# old_main_board.net
KiCad netlist of a schematic drawn in EAGLE
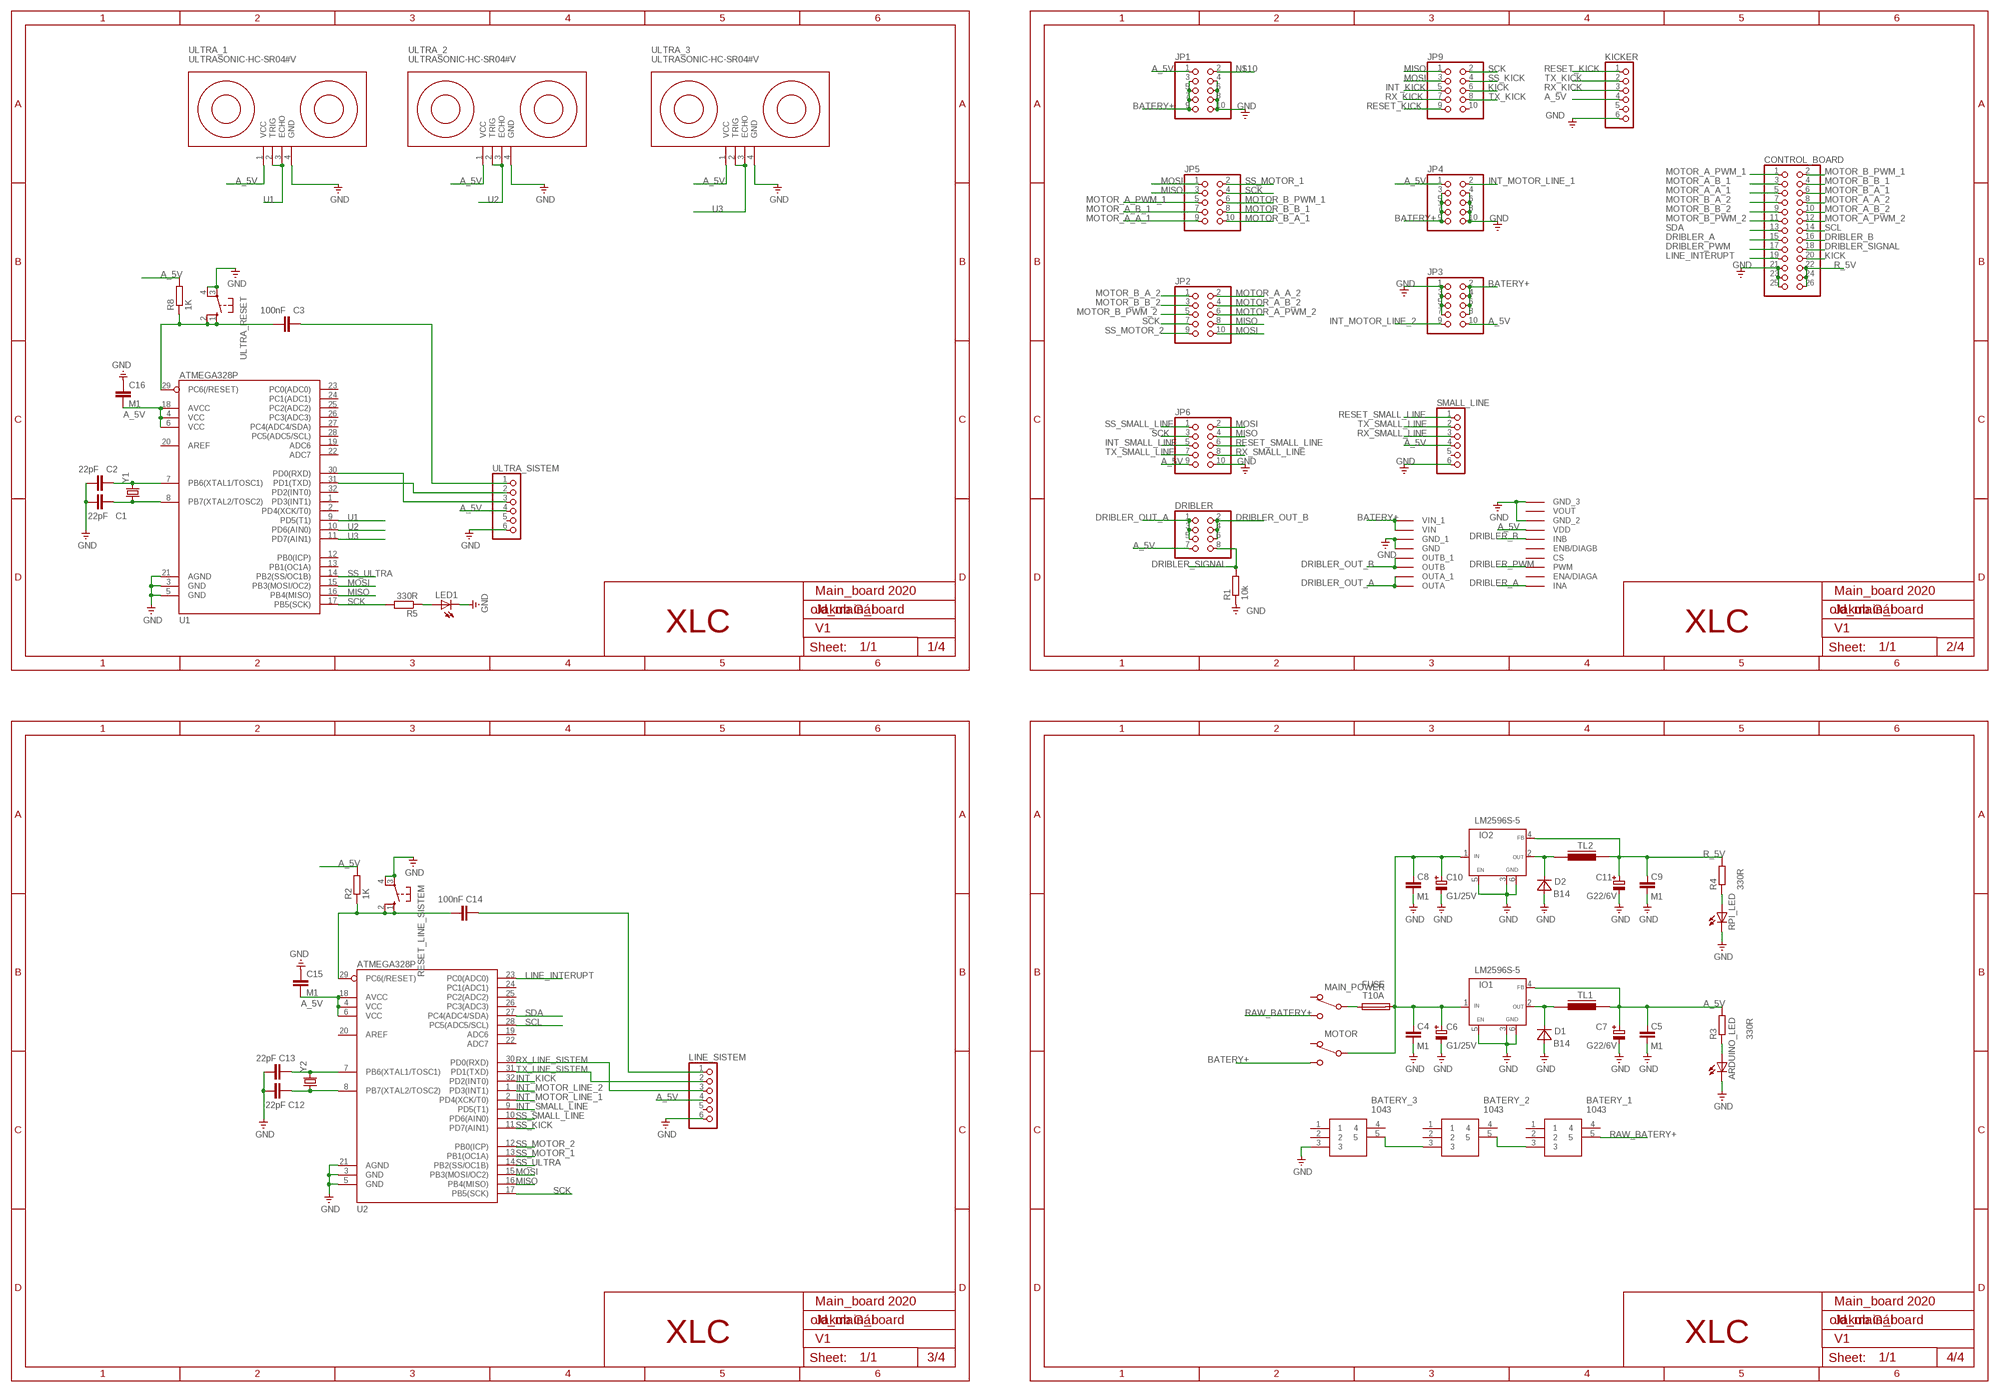
[diagram p0: schematic, sheet 1]

(export (version "E")
  (design (tool "Eeschema 10.0.6"))
  (components
    (comp (ref "ARDUINO_LED")
      (value "LEDCHIPLED_0603")
      (footprint "eagle-import:CHIPLED_0603")
      (libsource (lib "eagle-import") (part "LEDCHIPLED_0603"))
    )
    (comp (ref "BATERY_1")
      (value "1043")
      (footprint "eagle-import:1043")
      (fields (field (name "MOUSER_PART_NUMBER") "534-1043"))
      (libsource (lib "eagle-import") (part "1043"))
    )
    (comp (ref "BATERY_2")
      (value "1043")
      (footprint "eagle-import:1043")
      (fields (field (name "MOUSER_PART_NUMBER") "534-1043"))
      (libsource (lib "eagle-import") (part "1043"))
    )
    (comp (ref "BATERY_3")
      (value "1043")
      (footprint "eagle-import:1043")
      (fields (field (name "MOUSER_PART_NUMBER") "534-1043"))
      (libsource (lib "eagle-import") (part "1043"))
    )
    (comp (ref "C1")
      (value "22pF")
      (footprint "eagle-import:C0603")
      (libsource (lib "eagle-import") (part "rcl@1_C-EUC0603"))
    )
    (comp (ref "C2")
      (value "22pF")
      (footprint "eagle-import:C0603")
      (libsource (lib "eagle-import") (part "rcl@1_C-EUC0603"))
    )
    (comp (ref "C3")
      (value "100nF")
      (footprint "eagle-import:C0603")
      (libsource (lib "eagle-import") (part "rcl@1_C-EUC0603"))
    )
    (comp (ref "C4")
      (value "M1")
      (footprint "eagle-import:SMD-1206")
      (libsource (lib "eagle-import") (part "KOND-KERAM1206-SMD"))
    )
    (comp (ref "C5")
      (value "M1")
      (footprint "eagle-import:SMD-1206")
      (libsource (lib "eagle-import") (part "KOND-KERAM1206-SMD"))
    )
    (comp (ref "C6")
      (value "G1/25V")
      (footprint "eagle-import:SMD-ELE-D")
      (libsource (lib "eagle-import") (part "KOND-ELEKTD-SMD"))
    )
    (comp (ref "C7")
      (value "G22/6V")
      (footprint "eagle-import:SMD-ELE-D")
      (libsource (lib "eagle-import") (part "KOND-ELEKTD-SMD"))
    )
    (comp (ref "C8")
      (value "M1")
      (footprint "eagle-import:SMD-1206")
      (libsource (lib "eagle-import") (part "KOND-KERAM1206-SMD"))
    )
    (comp (ref "C9")
      (value "M1")
      (footprint "eagle-import:SMD-1206")
      (libsource (lib "eagle-import") (part "KOND-KERAM1206-SMD"))
    )
    (comp (ref "C10")
      (value "G1/25V")
      (footprint "eagle-import:SMD-ELE-D")
      (libsource (lib "eagle-import") (part "KOND-ELEKTD-SMD"))
    )
    (comp (ref "C11")
      (value "G22/6V")
      (footprint "eagle-import:SMD-ELE-D")
      (libsource (lib "eagle-import") (part "KOND-ELEKTD-SMD"))
    )
    (comp (ref "C12")
      (value "22pF")
      (footprint "eagle-import:C0603")
      (libsource (lib "eagle-import") (part "rcl@1_C-EUC0603"))
    )
    (comp (ref "C13")
      (value "22pF")
      (footprint "eagle-import:C0603")
      (libsource (lib "eagle-import") (part "rcl@1_C-EUC0603"))
    )
    (comp (ref "C14")
      (value "100nF")
      (footprint "eagle-import:C0603")
      (libsource (lib "eagle-import") (part "rcl@1_C-EUC0603"))
    )
    (comp (ref "C15")
      (value "M1")
      (footprint "eagle-import:C0603")
      (libsource (lib "eagle-import") (part "C-EUC0603"))
    )
    (comp (ref "C16")
      (value "M1")
      (footprint "eagle-import:C0603")
      (libsource (lib "eagle-import") (part "C-EUC0603"))
    )
    (comp (ref "CONTROL_BOARD")
      (value "PINHD-2X13_2.54")
      (footprint "eagle-import:2X13")
      (libsource (lib "eagle-import") (part "PINHD-2X13_2.54"))
    )
    (comp (ref "D1")
      (value "B14")
      (footprint "eagle-import:D-3,6X5,5")
      (libsource (lib "eagle-import") (part "DIODASMD-3,6X5,5"))
    )
    (comp (ref "D2")
      (value "B14")
      (footprint "eagle-import:D-3,6X5,5")
      (libsource (lib "eagle-import") (part "DIODASMD-3,6X5,5"))
    )
    (comp (ref "DRIBLER")
      (value "PINHD-2X4_2.54-SMD")
      (footprint "eagle-import:2X04SMD")
      (libsource (lib "eagle-import") (part "PINHD-2X4_2.54-SMD"))
    )
    (comp (ref "FUSE")
      (value "T10A")
      (footprint "eagle-import:SH22,5A")
      (libsource (lib "eagle-import") (part "POISTKA2A"))
    )
    (comp (ref "IO1")
      (value "LM2596S-5")
      (footprint "eagle-import:TO263-5")
      (libsource (lib "eagle-import") (part "LM2596S"))
    )
    (comp (ref "IO2")
      (value "LM2596S-5")
      (footprint "eagle-import:TO263-5")
      (libsource (lib "eagle-import") (part "LM2596S"))
    )
    (comp (ref "JP1")
      (value "PINHD-2X5IDC")
      (footprint "eagle-import:2X05_IDC")
      (libsource (lib "eagle-import") (part "PINHD-2X5IDC"))
    )
    (comp (ref "JP2")
      (value "PINHD-2X5IDC")
      (footprint "eagle-import:2X05_IDC")
      (libsource (lib "eagle-import") (part "PINHD-2X5IDC"))
    )
    (comp (ref "JP3")
      (value "PINHD-2X5IDC")
      (footprint "eagle-import:2X05_IDC")
      (libsource (lib "eagle-import") (part "PINHD-2X5IDC"))
    )
    (comp (ref "JP4")
      (value "PINHD-2X5IDC")
      (footprint "eagle-import:2X05_IDC")
      (libsource (lib "eagle-import") (part "PINHD-2X5IDC"))
    )
    (comp (ref "JP5")
      (value "PINHD-2X5IDC")
      (footprint "eagle-import:2X05_IDC")
      (libsource (lib "eagle-import") (part "PINHD-2X5IDC"))
    )
    (comp (ref "JP6")
      (value "PINHD-2X5IDC")
      (footprint "eagle-import:2X05_IDC")
      (libsource (lib "eagle-import") (part "PINHD-2X5IDC"))
    )
    (comp (ref "JP9")
      (value "PINHD-2X5IDC")
      (footprint "eagle-import:2X05_IDC")
      (libsource (lib "eagle-import") (part "PINHD-2X5IDC"))
    )
    (comp (ref "KICKER")
      (value "PINHD-1X6")
      (footprint "eagle-import:1X06")
      (libsource (lib "eagle-import") (part "PINHD-1X6"))
    )
    (comp (ref "LED1")
      (value "LEDCHIPLED_0603")
      (footprint "eagle-import:CHIPLED_0603")
      (libsource (lib "eagle-import") (part "LEDCHIPLED_0603"))
    )
    (comp (ref "LINE_SISTEM")
      (value "PINHD-1X6")
      (footprint "eagle-import:1X06")
      (libsource (lib "eagle-import") (part "PINHD-1X6"))
    )
    (comp (ref "MAIN_POWER")
      (value "PREP-1PB")
      (footprint "eagle-import:P-B069B")
      (libsource (lib "eagle-import") (part "PREP-1PB"))
    )
    (comp (ref "MOTOR")
      (value "PREP-1PB")
      (footprint "eagle-import:P-B069B")
      (libsource (lib "eagle-import") (part "PREP-1PB"))
    )
    (comp (ref "R1")
      (value "10k")
      (footprint "eagle-import:R0603")
      (libsource (lib "eagle-import") (part "R-EU_R0603"))
    )
    (comp (ref "R2")
      (value "1K")
      (footprint "eagle-import:R0603")
      (libsource (lib "eagle-import") (part "R-EU_R0603"))
    )
    (comp (ref "R3")
      (value "330R")
      (footprint "eagle-import:R0603")
      (libsource (lib "eagle-import") (part "R-EU_R0603"))
    )
    (comp (ref "R4")
      (value "330R")
      (footprint "eagle-import:R0603")
      (libsource (lib "eagle-import") (part "R-EU_R0603"))
    )
    (comp (ref "R5")
      (value "330R")
      (footprint "eagle-import:R0603")
      (libsource (lib "eagle-import") (part "R-EU_R0603"))
    )
    (comp (ref "R8")
      (value "1K")
      (footprint "eagle-import:R0603")
      (libsource (lib "eagle-import") (part "R-EU_R0603"))
    )
    (comp (ref "RESET_LINE_SISTEM")
      (value "10-XX")
      (footprint "eagle-import:B3F-10XX")
      (fields (field (name "MPN") "B3F-1000"))
      (libsource (lib "eagle-import") (part "10-XX"))
    )
    (comp (ref "RPI_LED")
      (value "LEDCHIPLED_0603")
      (footprint "eagle-import:CHIPLED_0603")
      (libsource (lib "eagle-import") (part "LEDCHIPLED_0603"))
    )
    (comp (ref "SMALL_LINE")
      (value "PINHD-1X6")
      (footprint "eagle-import:1X06")
      (libsource (lib "eagle-import") (part "PINHD-1X6"))
    )
    (comp (ref "TL1")
      (value "INDUK-TLSMD1")
      (footprint "eagle-import:INDUK-TL")
      (libsource (lib "eagle-import") (part "INDUK-TLSMD1"))
    )
    (comp (ref "TL2")
      (value "INDUK-TLSMD1")
      (footprint "eagle-import:INDUK-TL")
      (libsource (lib "eagle-import") (part "INDUK-TLSMD1"))
    )
    (comp (ref "U$4")
      (value "MOTOR_DRIVER")
      (footprint "eagle-import:MOTOR_DRIVER")
      (libsource (lib "eagle-import") (part "MOTOR_DRIVER"))
    )
    (comp (ref "U1")
      (value "ATMEGA328P")
      (footprint "eagle-import:TQFP32-08")
      (libsource (lib "eagle-import") (part "ATMEGA328_SMT"))
    )
    (comp (ref "U2")
      (value "ATMEGA328P")
      (footprint "eagle-import:TQFP32-08")
      (libsource (lib "eagle-import") (part "ATMEGA328_SMT"))
    )
    (comp (ref "ULTRA_1")
      (value "ULTRASONIC-HC-SR04#V")
      (footprint "eagle-import:ULTRASONIC-HC-SR04#V")
      (libsource (lib "eagle-import") (part "ULTRASONIC-HC-SR04#V"))
    )
    (comp (ref "ULTRA_2")
      (value "ULTRASONIC-HC-SR04#V")
      (footprint "eagle-import:ULTRASONIC-HC-SR04#V")
      (libsource (lib "eagle-import") (part "ULTRASONIC-HC-SR04#V"))
    )
    (comp (ref "ULTRA_3")
      (value "ULTRASONIC-HC-SR04#V")
      (footprint "eagle-import:ULTRASONIC-HC-SR04#V")
      (libsource (lib "eagle-import") (part "ULTRASONIC-HC-SR04#V"))
    )
    (comp (ref "ULTRA_RESET")
      (value "10-XX")
      (footprint "eagle-import:B3F-10XX")
      (fields (field (name "MPN") "B3F-1000"))
      (libsource (lib "eagle-import") (part "10-XX"))
    )
    (comp (ref "ULTRA_SISTEM")
      (value "PINHD-1X6")
      (footprint "eagle-import:1X06")
      (libsource (lib "eagle-import") (part "PINHD-1X6"))
    )
    (comp (ref "Y1")
      (value "CRYSTALHC49US")
      (footprint "eagle-import:HC49US")
      (libsource (lib "eagle-import") (part "CRYSTALHC49US"))
    )
    (comp (ref "Y2")
      (value "CRYSTALHC49US")
      (footprint "eagle-import:HC49US")
      (libsource (lib "eagle-import") (part "CRYSTALHC49US"))
    )
  )
  (nets
    (net (code "1") (name "/A_5V") (class "Default")
      (node (ref "C15") (pin "2") (pinfunction "2_2") (pintype "passive"))
      (node (ref "C16") (pin "2") (pinfunction "2_2") (pintype "passive"))
      (node (ref "C5") (pin "2") (pinfunction "2_2") (pintype "passive"))
      (node (ref "C7") (pin "PLUS") (pinfunction "PLUS_PLUS") (pintype "passive"))
      (node (ref "DRIBLER") (pin "7") (pinfunction "7_7") (pintype "passive"))
      (node (ref "IO1") (pin "4") (pinfunction "FB_4") (pintype "input"))
      (node (ref "JP1") (pin "1") (pinfunction "1_1") (pintype "passive"))
      (node (ref "JP3") (pin "10") (pinfunction "10_10") (pintype "passive"))
      (node (ref "JP4") (pin "1") (pinfunction "1_1") (pintype "passive"))
      (node (ref "JP6") (pin "9") (pinfunction "9_9") (pintype "passive"))
      (node (ref "KICKER") (pin "4") (pinfunction "4_4") (pintype "passive"))
      (node (ref "LINE_SISTEM") (pin "4") (pinfunction "4_4") (pintype "passive"))
      (node (ref "R2") (pin "2") (pinfunction "2_2") (pintype "passive"))
      (node (ref "R3") (pin "2") (pinfunction "2_2") (pintype "passive"))
      (node (ref "R8") (pin "2") (pinfunction "2_2") (pintype "passive"))
      (node (ref "SMALL_LINE") (pin "4") (pinfunction "4_4") (pintype "passive"))
      (node (ref "TL1") (pin "2") (pinfunction "2_2") (pintype "passive"))
      (node (ref "U$4") (pin "VDD") (pinfunction "VDD_VDD") (pintype "bidirectional"))
      (node (ref "U1") (pin "18") (pinfunction "AVCC_18") (pintype "bidirectional"))
      (node (ref "U1") (pin "4") (pinfunction "VCC_4") (pintype "bidirectional"))
      (node (ref "U1") (pin "6") (pinfunction "VCC_6") (pintype "bidirectional"))
      (node (ref "U2") (pin "18") (pinfunction "AVCC_18") (pintype "bidirectional"))
      (node (ref "U2") (pin "4") (pinfunction "VCC_4") (pintype "bidirectional"))
      (node (ref "U2") (pin "6") (pinfunction "VCC_6") (pintype "bidirectional"))
      (node (ref "ULTRA_1") (pin "1") (pinfunction "VCC_1") (pintype "power_in"))
      (node (ref "ULTRA_2") (pin "1") (pinfunction "VCC_1") (pintype "power_in"))
      (node (ref "ULTRA_3") (pin "1") (pinfunction "VCC_1") (pintype "power_in"))
      (node (ref "ULTRA_SISTEM") (pin "4") (pinfunction "4_4") (pintype "passive"))
    )
    (net (code "2") (name "/BATERY+") (class "Default")
      (node (ref "JP1") (pin "3") (pinfunction "3_3") (pintype "passive"))
      (node (ref "JP1") (pin "5") (pinfunction "5_5") (pintype "passive"))
      (node (ref "JP1") (pin "7") (pinfunction "7_7") (pintype "passive"))
      (node (ref "JP1") (pin "9") (pinfunction "9_9") (pintype "passive"))
      (node (ref "JP3") (pin "2") (pinfunction "2_2") (pintype "passive"))
      (node (ref "JP3") (pin "4") (pinfunction "4_4") (pintype "passive"))
      (node (ref "JP3") (pin "6") (pinfunction "6_6") (pintype "passive"))
      (node (ref "JP3") (pin "8") (pinfunction "8_8") (pintype "passive"))
      (node (ref "JP4") (pin "3") (pinfunction "3_3") (pintype "passive"))
      (node (ref "JP4") (pin "5") (pinfunction "5_5") (pintype "passive"))
      (node (ref "JP4") (pin "7") (pinfunction "7_7") (pintype "passive"))
      (node (ref "JP4") (pin "9") (pinfunction "9_9") (pintype "passive"))
      (node (ref "MOTOR") (pin "1") (pinfunction "1-OFF_1") (pintype "passive"))
      (node (ref "U$4") (pin "VIN") (pinfunction "VIN_VIN") (pintype "bidirectional"))
      (node (ref "U$4") (pin "VIN_1") (pinfunction "VIN_1_VIN_1") (pintype "bidirectional"))
    )
    (net (code "3") (name "/DRIBLER_A") (class "Default")
      (node (ref "CONTROL_BOARD") (pin "15") (pinfunction "15_15") (pintype "passive"))
      (node (ref "U$4") (pin "INA") (pinfunction "INA_INA") (pintype "bidirectional"))
    )
    (net (code "4") (name "/DRIBLER_B") (class "Default")
      (node (ref "CONTROL_BOARD") (pin "16") (pinfunction "16_16") (pintype "passive"))
      (node (ref "U$4") (pin "INB") (pinfunction "INB_INB") (pintype "bidirectional"))
    )
    (net (code "5") (name "/DRIBLER_OUT_A") (class "Default")
      (node (ref "DRIBLER") (pin "1") (pinfunction "1_1") (pintype "passive"))
      (node (ref "DRIBLER") (pin "3") (pinfunction "3_3") (pintype "passive"))
      (node (ref "DRIBLER") (pin "5") (pinfunction "5_5") (pintype "passive"))
      (node (ref "U$4") (pin "OUTA") (pinfunction "OUTA_OUTA") (pintype "bidirectional"))
      (node (ref "U$4") (pin "OUTA_1") (pinfunction "OUTA_1_OUTA_1") (pintype "bidirectional"))
    )
    (net (code "6") (name "/DRIBLER_OUT_B") (class "Default")
      (node (ref "DRIBLER") (pin "2") (pinfunction "2_2") (pintype "passive"))
      (node (ref "DRIBLER") (pin "4") (pinfunction "4_4") (pintype "passive"))
      (node (ref "DRIBLER") (pin "6") (pinfunction "6_6") (pintype "passive"))
      (node (ref "U$4") (pin "OUTB") (pinfunction "OUTB_OUTB") (pintype "bidirectional"))
      (node (ref "U$4") (pin "OUTB_1") (pinfunction "OUTB_1_OUTB_1") (pintype "bidirectional"))
    )
    (net (code "7") (name "/DRIBLER_PWM") (class "Default")
      (node (ref "CONTROL_BOARD") (pin "17") (pinfunction "17_17") (pintype "passive"))
      (node (ref "U$4") (pin "PWM") (pinfunction "PWM_PWM") (pintype "bidirectional"))
    )
    (net (code "8") (name "/DRIBLER_SIGNAL") (class "Default")
      (node (ref "CONTROL_BOARD") (pin "18") (pinfunction "18_18") (pintype "passive"))
      (node (ref "DRIBLER") (pin "8") (pinfunction "8_8") (pintype "passive"))
      (node (ref "R1") (pin "2") (pinfunction "2_2") (pintype "passive"))
    )
    (net (code "9") (name "/INT_KICK") (class "Default")
      (node (ref "JP9") (pin "5") (pinfunction "5_5") (pintype "passive"))
      (node (ref "U2") (pin "32") (pinfunction "PD2(INT0)_32") (pintype "bidirectional"))
    )
    (net (code "10") (name "/INT_MOTOR_LINE_1") (class "Default")
      (node (ref "JP4") (pin "2") (pinfunction "2_2") (pintype "passive"))
      (node (ref "U2") (pin "2") (pinfunction "PD4(XCK/T0)_2") (pintype "bidirectional"))
    )
    (net (code "11") (name "/INT_MOTOR_LINE_2") (class "Default")
      (node (ref "JP3") (pin "9") (pinfunction "9_9") (pintype "passive"))
      (node (ref "U2") (pin "1") (pinfunction "PD3(INT1)_1") (pintype "bidirectional"))
    )
    (net (code "12") (name "/INT_SMALL_LINE") (class "Default")
      (node (ref "JP6") (pin "5") (pinfunction "5_5") (pintype "passive"))
      (node (ref "U2") (pin "9") (pinfunction "PD5(T1)_9") (pintype "bidirectional"))
    )
    (net (code "13") (name "/KICK") (class "Default")
      (node (ref "CONTROL_BOARD") (pin "20") (pinfunction "20_20") (pintype "passive"))
      (node (ref "JP9") (pin "6") (pinfunction "6_6") (pintype "passive"))
    )
    (net (code "14") (name "/LINE_INTERUPT") (class "Default")
      (node (ref "CONTROL_BOARD") (pin "19") (pinfunction "19_19") (pintype "passive"))
      (node (ref "U2") (pin "23") (pinfunction "PC0(ADC0)_23") (pintype "bidirectional"))
    )
    (net (code "15") (name "/MISO") (class "Default")
      (node (ref "JP2") (pin "8") (pinfunction "8_8") (pintype "passive"))
      (node (ref "JP5") (pin "3") (pinfunction "3_3") (pintype "passive"))
      (node (ref "JP6") (pin "4") (pinfunction "4_4") (pintype "passive"))
      (node (ref "JP9") (pin "1") (pinfunction "1_1") (pintype "passive"))
      (node (ref "U1") (pin "16") (pinfunction "PB4(MISO)_16") (pintype "bidirectional"))
      (node (ref "U2") (pin "16") (pinfunction "PB4(MISO)_16") (pintype "bidirectional"))
    )
    (net (code "16") (name "/MOSI") (class "Default")
      (node (ref "JP2") (pin "10") (pinfunction "10_10") (pintype "passive"))
      (node (ref "JP5") (pin "1") (pinfunction "1_1") (pintype "passive"))
      (node (ref "JP6") (pin "2") (pinfunction "2_2") (pintype "passive"))
      (node (ref "JP9") (pin "3") (pinfunction "3_3") (pintype "passive"))
      (node (ref "U1") (pin "15") (pinfunction "PB3(MOSI/OC2)_15") (pintype "bidirectional"))
      (node (ref "U2") (pin "15") (pinfunction "PB3(MOSI/OC2)_15") (pintype "bidirectional"))
    )
    (net (code "17") (name "/MOTOR_A_A_1") (class "Default")
      (node (ref "CONTROL_BOARD") (pin "5") (pinfunction "5_5") (pintype "passive"))
      (node (ref "JP5") (pin "9") (pinfunction "9_9") (pintype "passive"))
    )
    (net (code "18") (name "/MOTOR_A_A_2") (class "Default")
      (node (ref "CONTROL_BOARD") (pin "8") (pinfunction "8_8") (pintype "passive"))
      (node (ref "JP2") (pin "2") (pinfunction "2_2") (pintype "passive"))
    )
    (net (code "19") (name "/MOTOR_A_B_1") (class "Default")
      (node (ref "CONTROL_BOARD") (pin "3") (pinfunction "3_3") (pintype "passive"))
      (node (ref "JP5") (pin "7") (pinfunction "7_7") (pintype "passive"))
    )
    (net (code "20") (name "/MOTOR_A_B_2") (class "Default")
      (node (ref "CONTROL_BOARD") (pin "10") (pinfunction "10_10") (pintype "passive"))
      (node (ref "JP2") (pin "4") (pinfunction "4_4") (pintype "passive"))
    )
    (net (code "21") (name "/MOTOR_A_PWM_1") (class "Default")
      (node (ref "CONTROL_BOARD") (pin "1") (pinfunction "1_1") (pintype "passive"))
      (node (ref "JP5") (pin "5") (pinfunction "5_5") (pintype "passive"))
    )
    (net (code "22") (name "/MOTOR_A_PWM_2") (class "Default")
      (node (ref "CONTROL_BOARD") (pin "12") (pinfunction "12_12") (pintype "passive"))
      (node (ref "JP2") (pin "6") (pinfunction "6_6") (pintype "passive"))
    )
    (net (code "23") (name "/MOTOR_B_A_1") (class "Default")
      (node (ref "CONTROL_BOARD") (pin "6") (pinfunction "6_6") (pintype "passive"))
      (node (ref "JP5") (pin "10") (pinfunction "10_10") (pintype "passive"))
    )
    (net (code "24") (name "/MOTOR_B_A_2") (class "Default")
      (node (ref "CONTROL_BOARD") (pin "7") (pinfunction "7_7") (pintype "passive"))
      (node (ref "JP2") (pin "1") (pinfunction "1_1") (pintype "passive"))
    )
    (net (code "25") (name "/MOTOR_B_B_1") (class "Default")
      (node (ref "CONTROL_BOARD") (pin "4") (pinfunction "4_4") (pintype "passive"))
      (node (ref "JP5") (pin "8") (pinfunction "8_8") (pintype "passive"))
    )
    (net (code "26") (name "/MOTOR_B_B_2") (class "Default")
      (node (ref "CONTROL_BOARD") (pin "9") (pinfunction "9_9") (pintype "passive"))
      (node (ref "JP2") (pin "3") (pinfunction "3_3") (pintype "passive"))
    )
    (net (code "27") (name "/MOTOR_B_PWM_1") (class "Default")
      (node (ref "CONTROL_BOARD") (pin "2") (pinfunction "2_2") (pintype "passive"))
      (node (ref "JP5") (pin "6") (pinfunction "6_6") (pintype "passive"))
    )
    (net (code "28") (name "/MOTOR_B_PWM_2") (class "Default")
      (node (ref "CONTROL_BOARD") (pin "11") (pinfunction "11_11") (pintype "passive"))
      (node (ref "JP2") (pin "5") (pinfunction "5_5") (pintype "passive"))
    )
    (net (code "29") (name "/N$10") (class "Default")
      (node (ref "JP1") (pin "2") (pinfunction "2_2") (pintype "passive"))
    )
    (net (code "30") (name "/RAW_BATERY+") (class "Default")
      (node (ref "BATERY_1") (pin "5") (pinfunction "5_5") (pintype "bidirectional"))
      (node (ref "MAIN_POWER") (pin "1") (pinfunction "1-OFF_1") (pintype "passive"))
    )
    (net (code "31") (name "/RESET_KICK") (class "Default")
      (node (ref "JP9") (pin "9") (pinfunction "9_9") (pintype "passive"))
      (node (ref "KICKER") (pin "1") (pinfunction "1_1") (pintype "passive"))
    )
    (net (code "32") (name "/RESET_SMALL_LINE") (class "Default")
      (node (ref "JP6") (pin "6") (pinfunction "6_6") (pintype "passive"))
      (node (ref "SMALL_LINE") (pin "1") (pinfunction "1_1") (pintype "passive"))
    )
    (net (code "33") (name "/RX_KICK") (class "Default")
      (node (ref "JP9") (pin "7") (pinfunction "7_7") (pintype "passive"))
      (node (ref "KICKER") (pin "3") (pinfunction "3_3") (pintype "passive"))
    )
    (net (code "34") (name "/RX_LINE_SISTEM") (class "Default")
      (node (ref "LINE_SISTEM") (pin "3") (pinfunction "3_3") (pintype "passive"))
      (node (ref "U2") (pin "30") (pinfunction "PD0(RXD)_30") (pintype "bidirectional"))
    )
    (net (code "35") (name "/RX_SMALL_LINE") (class "Default")
      (node (ref "JP6") (pin "8") (pinfunction "8_8") (pintype "passive"))
      (node (ref "SMALL_LINE") (pin "3") (pinfunction "3_3") (pintype "passive"))
    )
    (net (code "36") (name "/R_5V") (class "Default")
      (node (ref "C11") (pin "PLUS") (pinfunction "PLUS_PLUS") (pintype "passive"))
      (node (ref "C9") (pin "2") (pinfunction "2_2") (pintype "passive"))
      (node (ref "CONTROL_BOARD") (pin "22") (pinfunction "22_22") (pintype "passive"))
      (node (ref "CONTROL_BOARD") (pin "24") (pinfunction "24_24") (pintype "passive"))
      (node (ref "CONTROL_BOARD") (pin "26") (pinfunction "26_26") (pintype "passive"))
      (node (ref "IO2") (pin "4") (pinfunction "FB_4") (pintype "input"))
      (node (ref "R4") (pin "2") (pinfunction "2_2") (pintype "passive"))
      (node (ref "TL2") (pin "2") (pinfunction "2_2") (pintype "passive"))
    )
    (net (code "37") (name "/SCK") (class "Default")
      (node (ref "JP2") (pin "7") (pinfunction "7_7") (pintype "passive"))
      (node (ref "JP5") (pin "4") (pinfunction "4_4") (pintype "passive"))
      (node (ref "JP6") (pin "3") (pinfunction "3_3") (pintype "passive"))
      (node (ref "JP9") (pin "2") (pinfunction "2_2") (pintype "passive"))
      (node (ref "R5") (pin "2") (pinfunction "2_2") (pintype "passive"))
      (node (ref "U1") (pin "17") (pinfunction "PB5(SCK)_17") (pintype "bidirectional"))
      (node (ref "U2") (pin "17") (pinfunction "PB5(SCK)_17") (pintype "bidirectional"))
    )
    (net (code "38") (name "/SCL") (class "Default")
      (node (ref "CONTROL_BOARD") (pin "14") (pinfunction "14_14") (pintype "passive"))
      (node (ref "U2") (pin "28") (pinfunction "PC5(ADC5/SCL)_28") (pintype "bidirectional"))
    )
    (net (code "39") (name "/SDA") (class "Default")
      (node (ref "CONTROL_BOARD") (pin "13") (pinfunction "13_13") (pintype "passive"))
      (node (ref "U2") (pin "27") (pinfunction "PC4(ADC4/SDA)_27") (pintype "bidirectional"))
    )
    (net (code "40") (name "/SS_KICK") (class "Default")
      (node (ref "JP9") (pin "4") (pinfunction "4_4") (pintype "passive"))
      (node (ref "U2") (pin "11") (pinfunction "PD7(AIN1)_11") (pintype "bidirectional"))
    )
    (net (code "41") (name "/SS_MOTOR_1") (class "Default")
      (node (ref "JP5") (pin "2") (pinfunction "2_2") (pintype "passive"))
      (node (ref "U2") (pin "13") (pinfunction "PB1(OC1A)_13") (pintype "bidirectional"))
    )
    (net (code "42") (name "/SS_MOTOR_2") (class "Default")
      (node (ref "JP2") (pin "9") (pinfunction "9_9") (pintype "passive"))
      (node (ref "U2") (pin "12") (pinfunction "PB0(ICP)_12") (pintype "bidirectional"))
    )
    (net (code "43") (name "/SS_SMALL_LINE") (class "Default")
      (node (ref "JP6") (pin "1") (pinfunction "1_1") (pintype "passive"))
      (node (ref "U2") (pin "10") (pinfunction "PD6(AIN0)_10") (pintype "bidirectional"))
    )
    (net (code "44") (name "/SS_ULTRA") (class "Default")
      (node (ref "U1") (pin "14") (pinfunction "PB2(SS/OC1B)_14") (pintype "bidirectional"))
      (node (ref "U2") (pin "14") (pinfunction "PB2(SS/OC1B)_14") (pintype "bidirectional"))
    )
    (net (code "45") (name "/TX_KICK") (class "Default")
      (node (ref "JP9") (pin "8") (pinfunction "8_8") (pintype "passive"))
      (node (ref "KICKER") (pin "2") (pinfunction "2_2") (pintype "passive"))
    )
    (net (code "46") (name "/TX_LINE_SISTEM") (class "Default")
      (node (ref "LINE_SISTEM") (pin "2") (pinfunction "2_2") (pintype "passive"))
      (node (ref "U2") (pin "31") (pinfunction "PD1(TXD)_31") (pintype "bidirectional"))
    )
    (net (code "47") (name "/TX_SMALL_LINE") (class "Default")
      (node (ref "JP6") (pin "7") (pinfunction "7_7") (pintype "passive"))
      (node (ref "SMALL_LINE") (pin "2") (pinfunction "2_2") (pintype "passive"))
    )
    (net (code "48") (name "/U1") (class "Default")
      (node (ref "U1") (pin "9") (pinfunction "PD5(T1)_9") (pintype "bidirectional"))
      (node (ref "ULTRA_1") (pin "2") (pinfunction "TRIG_2") (pintype "input"))
      (node (ref "ULTRA_1") (pin "3") (pinfunction "ECHO_3") (pintype "output"))
    )
    (net (code "49") (name "/U2") (class "Default")
      (node (ref "U1") (pin "10") (pinfunction "PD6(AIN0)_10") (pintype "bidirectional"))
      (node (ref "ULTRA_2") (pin "2") (pinfunction "TRIG_2") (pintype "input"))
      (node (ref "ULTRA_2") (pin "3") (pinfunction "ECHO_3") (pintype "output"))
    )
    (net (code "50") (name "/U3") (class "Default")
      (node (ref "U1") (pin "11") (pinfunction "PD7(AIN1)_11") (pintype "bidirectional"))
      (node (ref "ULTRA_3") (pin "2") (pinfunction "TRIG_2") (pintype "input"))
      (node (ref "ULTRA_3") (pin "3") (pinfunction "ECHO_3") (pintype "output"))
    )
    (net (code "51") (name "GND") (class "Default")
      (node (ref "ARDUINO_LED") (pin "C") (pinfunction "C_C") (pintype "passive"))
      (node (ref "BATERY_3") (pin "3") (pinfunction "3_3") (pintype "bidirectional"))
      (node (ref "C1") (pin "1") (pinfunction "1_1") (pintype "passive"))
      (node (ref "C10") (pin "MINUS") (pinfunction "MINUS_MINUS") (pintype "passive"))
      (node (ref "C11") (pin "MINUS") (pinfunction "MINUS_MINUS") (pintype "passive"))
      (node (ref "C12") (pin "1") (pinfunction "1_1") (pintype "passive"))
      (node (ref "C13") (pin "1") (pinfunction "1_1") (pintype "passive"))
      (node (ref "C15") (pin "1") (pinfunction "1_1") (pintype "passive"))
      (node (ref "C16") (pin "1") (pinfunction "1_1") (pintype "passive"))
      (node (ref "C2") (pin "1") (pinfunction "1_1") (pintype "passive"))
      (node (ref "C4") (pin "1") (pinfunction "1_1") (pintype "passive"))
      (node (ref "C5") (pin "1") (pinfunction "1_1") (pintype "passive"))
      (node (ref "C6") (pin "MINUS") (pinfunction "MINUS_MINUS") (pintype "passive"))
      (node (ref "C7") (pin "MINUS") (pinfunction "MINUS_MINUS") (pintype "passive"))
      (node (ref "C8") (pin "1") (pinfunction "1_1") (pintype "passive"))
      (node (ref "C9") (pin "1") (pinfunction "1_1") (pintype "passive"))
      (node (ref "CONTROL_BOARD") (pin "21") (pinfunction "21_21") (pintype "passive"))
      (node (ref "CONTROL_BOARD") (pin "23") (pinfunction "23_23") (pintype "passive"))
      (node (ref "CONTROL_BOARD") (pin "25") (pinfunction "25_25") (pintype "passive"))
      (node (ref "D1") (pin "A") (pinfunction "A_A") (pintype "passive"))
      (node (ref "D2") (pin "A") (pinfunction "A_A") (pintype "passive"))
      (node (ref "IO1") (pin "3") (pinfunction "GND_3") (pintype "power_in"))
      (node (ref "IO1") (pin "5") (pinfunction "EN_5") (pintype "input"))
      (node (ref "IO1") (pin "6") (pinfunction "GND_6") (pintype "power_in"))
      (node (ref "IO2") (pin "3") (pinfunction "GND_3") (pintype "power_in"))
      (node (ref "IO2") (pin "5") (pinfunction "EN_5") (pintype "input"))
      (node (ref "IO2") (pin "6") (pinfunction "GND_6") (pintype "power_in"))
      (node (ref "JP1") (pin "10") (pinfunction "10_10") (pintype "passive"))
      (node (ref "JP1") (pin "4") (pinfunction "4_4") (pintype "passive"))
      (node (ref "JP1") (pin "6") (pinfunction "6_6") (pintype "passive"))
      (node (ref "JP1") (pin "8") (pinfunction "8_8") (pintype "passive"))
      (node (ref "JP3") (pin "1") (pinfunction "1_1") (pintype "passive"))
      (node (ref "JP3") (pin "3") (pinfunction "3_3") (pintype "passive"))
      (node (ref "JP3") (pin "5") (pinfunction "5_5") (pintype "passive"))
      (node (ref "JP3") (pin "7") (pinfunction "7_7") (pintype "passive"))
      (node (ref "JP4") (pin "10") (pinfunction "10_10") (pintype "passive"))
      (node (ref "JP4") (pin "4") (pinfunction "4_4") (pintype "passive"))
      (node (ref "JP4") (pin "6") (pinfunction "6_6") (pintype "passive"))
      (node (ref "JP4") (pin "8") (pinfunction "8_8") (pintype "passive"))
      (node (ref "JP6") (pin "10") (pinfunction "10_10") (pintype "passive"))
      (node (ref "KICKER") (pin "6") (pinfunction "6_6") (pintype "passive"))
      (node (ref "LED1") (pin "C") (pinfunction "C_C") (pintype "passive"))
      (node (ref "LINE_SISTEM") (pin "6") (pinfunction "6_6") (pintype "passive"))
      (node (ref "R1") (pin "1") (pinfunction "1_1") (pintype "passive"))
      (node (ref "RESET_LINE_SISTEM") (pin "3") (pinfunction "P_3") (pintype "passive"))
      (node (ref "RESET_LINE_SISTEM") (pin "4") (pinfunction "P1_4") (pintype "passive"))
      (node (ref "RPI_LED") (pin "C") (pinfunction "C_C") (pintype "passive"))
      (node (ref "SMALL_LINE") (pin "6") (pinfunction "6_6") (pintype "passive"))
      (node (ref "U$4") (pin "GND") (pinfunction "GND_GND") (pintype "bidirectional"))
      (node (ref "U$4") (pin "GND_1") (pinfunction "GND_1_GND_1") (pintype "bidirectional"))
      (node (ref "U$4") (pin "GND_2") (pinfunction "GND_2_GND_2") (pintype "bidirectional"))
      (node (ref "U$4") (pin "GND_3") (pinfunction "GND_3_GND_3") (pintype "bidirectional"))
      (node (ref "U1") (pin "21") (pinfunction "AGND_21") (pintype "bidirectional"))
      (node (ref "U1") (pin "3") (pinfunction "GND_3") (pintype "bidirectional"))
      (node (ref "U1") (pin "5") (pinfunction "GND_5") (pintype "bidirectional"))
      (node (ref "U2") (pin "21") (pinfunction "AGND_21") (pintype "bidirectional"))
      (node (ref "U2") (pin "3") (pinfunction "GND_3") (pintype "bidirectional"))
      (node (ref "U2") (pin "5") (pinfunction "GND_5") (pintype "bidirectional"))
      (node (ref "ULTRA_1") (pin "4") (pinfunction "GND_4") (pintype "power_in"))
      (node (ref "ULTRA_2") (pin "4") (pinfunction "GND_4") (pintype "power_in"))
      (node (ref "ULTRA_3") (pin "4") (pinfunction "GND_4") (pintype "power_in"))
      (node (ref "ULTRA_RESET") (pin "3") (pinfunction "P_3") (pintype "passive"))
      (node (ref "ULTRA_RESET") (pin "4") (pinfunction "P1_4") (pintype "passive"))
      (node (ref "ULTRA_SISTEM") (pin "6") (pinfunction "6_6") (pintype "passive"))
    )
    (net (code "52") (name "Net-(ARDUINO_LED-PadA)") (class "Default")
      (node (ref "ARDUINO_LED") (pin "A") (pinfunction "A_A") (pintype "passive"))
      (node (ref "R3") (pin "1") (pinfunction "1_1") (pintype "passive"))
    )
    (net (code "53") (name "Net-(BATERY_1-Pad3)") (class "Default")
      (node (ref "BATERY_1") (pin "3") (pinfunction "3_3") (pintype "bidirectional"))
      (node (ref "BATERY_2") (pin "5") (pinfunction "5_5") (pintype "bidirectional"))
    )
    (net (code "54") (name "Net-(BATERY_2-Pad3)") (class "Default")
      (node (ref "BATERY_2") (pin "3") (pinfunction "3_3") (pintype "bidirectional"))
      (node (ref "BATERY_3") (pin "5") (pinfunction "5_5") (pintype "bidirectional"))
    )
    (net (code "55") (name "Net-(C3-Pad2)") (class "Default")
      (node (ref "C3") (pin "2") (pinfunction "2_2") (pintype "passive"))
      (node (ref "ULTRA_SISTEM") (pin "1") (pinfunction "1_1") (pintype "passive"))
    )
    (net (code "56") (name "Net-(C14-Pad2)") (class "Default")
      (node (ref "C14") (pin "2") (pinfunction "2_2") (pintype "passive"))
      (node (ref "LINE_SISTEM") (pin "1") (pinfunction "1_1") (pintype "passive"))
    )
    (net (code "57") (name "Net-(IO1-IN)") (class "Default")
      (node (ref "C10") (pin "PLUS") (pinfunction "PLUS_PLUS") (pintype "passive"))
      (node (ref "C4") (pin "2") (pinfunction "2_2") (pintype "passive"))
      (node (ref "C6") (pin "PLUS") (pinfunction "PLUS_PLUS") (pintype "passive"))
      (node (ref "C8") (pin "2") (pinfunction "2_2") (pintype "passive"))
      (node (ref "FUSE") (pin "2") (pinfunction "2_2") (pintype "passive"))
      (node (ref "IO1") (pin "1") (pinfunction "IN_1") (pintype "input"))
      (node (ref "IO2") (pin "1") (pinfunction "IN_1") (pintype "input"))
      (node (ref "MOTOR") (pin "2") (pinfunction "2-COM_2") (pintype "passive"))
    )
    (net (code "58") (name "Net-(IO1-OUT)") (class "Default")
      (node (ref "D1") (pin "K") (pinfunction "K_K") (pintype "passive"))
      (node (ref "IO1") (pin "2") (pinfunction "OUT_2") (pintype "output"))
      (node (ref "TL1") (pin "1") (pinfunction "1_1") (pintype "passive"))
    )
    (net (code "59") (name "Net-(IO2-OUT)") (class "Default")
      (node (ref "D2") (pin "K") (pinfunction "K_K") (pintype "passive"))
      (node (ref "IO2") (pin "2") (pinfunction "OUT_2") (pintype "output"))
      (node (ref "TL2") (pin "1") (pinfunction "1_1") (pintype "passive"))
    )
    (net (code "60") (name "Net-(LED1-PadA)") (class "Default")
      (node (ref "LED1") (pin "A") (pinfunction "A_A") (pintype "passive"))
      (node (ref "R5") (pin "1") (pinfunction "1_1") (pintype "passive"))
    )
    (net (code "61") (name "Net-(MAIN_POWER-2-COM)") (class "Default")
      (node (ref "FUSE") (pin "1") (pinfunction "1_1") (pintype "passive"))
      (node (ref "MAIN_POWER") (pin "2") (pinfunction "2-COM_2") (pintype "passive"))
    )
    (net (code "62") (name "Net-(R4-Pad1)") (class "Default")
      (node (ref "R4") (pin "1") (pinfunction "1_1") (pintype "passive"))
      (node (ref "RPI_LED") (pin "A") (pinfunction "A_A") (pintype "passive"))
    )
    (net (code "63") (name "Net-(RESET_LINE_SISTEM-S)") (class "Default")
      (node (ref "C14") (pin "1") (pinfunction "1_1") (pintype "passive"))
      (node (ref "R2") (pin "1") (pinfunction "1_1") (pintype "passive"))
      (node (ref "RESET_LINE_SISTEM") (pin "1") (pinfunction "S_1") (pintype "passive"))
      (node (ref "RESET_LINE_SISTEM") (pin "2") (pinfunction "S1_2") (pintype "passive"))
      (node (ref "U2") (pin "29") (pinfunction "PC6(/RESET)_29") (pintype "bidirectional"))
    )
    (net (code "64") (name "Net-(U1-PB6(XTAL1{slash}TOSC1))") (class "Default")
      (node (ref "C2") (pin "2") (pinfunction "2_2") (pintype "passive"))
      (node (ref "U1") (pin "7") (pinfunction "PB6(XTAL1/TOSC1)_7") (pintype "bidirectional"))
      (node (ref "Y1") (pin "2") (pinfunction "2_2") (pintype "passive"))
    )
    (net (code "65") (name "Net-(U1-PB7(XTAL2{slash}TOSC2))") (class "Default")
      (node (ref "C1") (pin "2") (pinfunction "2_2") (pintype "passive"))
      (node (ref "U1") (pin "8") (pinfunction "PB7(XTAL2/TOSC2)_8") (pintype "bidirectional"))
      (node (ref "Y1") (pin "1") (pinfunction "1_1") (pintype "passive"))
    )
    (net (code "66") (name "Net-(U1-PC6({slash}RESET))") (class "Default")
      (node (ref "C3") (pin "1") (pinfunction "1_1") (pintype "passive"))
      (node (ref "R8") (pin "1") (pinfunction "1_1") (pintype "passive"))
      (node (ref "U1") (pin "29") (pinfunction "PC6(/RESET)_29") (pintype "bidirectional"))
      (node (ref "ULTRA_RESET") (pin "1") (pinfunction "S_1") (pintype "passive"))
      (node (ref "ULTRA_RESET") (pin "2") (pinfunction "S1_2") (pintype "passive"))
    )
    (net (code "67") (name "Net-(U1-PD0(RXD))") (class "Default")
      (node (ref "U1") (pin "30") (pinfunction "PD0(RXD)_30") (pintype "bidirectional"))
      (node (ref "ULTRA_SISTEM") (pin "3") (pinfunction "3_3") (pintype "passive"))
    )
    (net (code "68") (name "Net-(U1-PD1(TXD))") (class "Default")
      (node (ref "U1") (pin "31") (pinfunction "PD1(TXD)_31") (pintype "bidirectional"))
      (node (ref "ULTRA_SISTEM") (pin "2") (pinfunction "2_2") (pintype "passive"))
    )
    (net (code "69") (name "Net-(U2-PB6(XTAL1{slash}TOSC1))") (class "Default")
      (node (ref "C13") (pin "2") (pinfunction "2_2") (pintype "passive"))
      (node (ref "U2") (pin "7") (pinfunction "PB6(XTAL1/TOSC1)_7") (pintype "bidirectional"))
      (node (ref "Y2") (pin "2") (pinfunction "2_2") (pintype "passive"))
    )
    (net (code "70") (name "Net-(U2-PB7(XTAL2{slash}TOSC2))") (class "Default")
      (node (ref "C12") (pin "2") (pinfunction "2_2") (pintype "passive"))
      (node (ref "U2") (pin "8") (pinfunction "PB7(XTAL2/TOSC2)_8") (pintype "bidirectional"))
      (node (ref "Y2") (pin "1") (pinfunction "1_1") (pintype "passive"))
    )
    (net (code "71") (name "unconnected-(BATERY_1-Pad1)") (class "Default")
      (node (ref "BATERY_1") (pin "1") (pinfunction "1_1") (pintype "bidirectional"))
    )
    (net (code "72") (name "unconnected-(BATERY_1-Pad2)") (class "Default")
      (node (ref "BATERY_1") (pin "2") (pinfunction "2_2") (pintype "bidirectional"))
    )
    (net (code "73") (name "unconnected-(BATERY_1-Pad4)") (class "Default")
      (node (ref "BATERY_1") (pin "4") (pinfunction "4_4") (pintype "bidirectional"))
    )
    (net (code "74") (name "unconnected-(BATERY_2-Pad1)") (class "Default")
      (node (ref "BATERY_2") (pin "1") (pinfunction "1_1") (pintype "bidirectional"))
    )
    (net (code "75") (name "unconnected-(BATERY_2-Pad2)") (class "Default")
      (node (ref "BATERY_2") (pin "2") (pinfunction "2_2") (pintype "bidirectional"))
    )
    (net (code "76") (name "unconnected-(BATERY_2-Pad4)") (class "Default")
      (node (ref "BATERY_2") (pin "4") (pinfunction "4_4") (pintype "bidirectional"))
    )
    (net (code "77") (name "unconnected-(BATERY_3-Pad1)") (class "Default")
      (node (ref "BATERY_3") (pin "1") (pinfunction "1_1") (pintype "bidirectional"))
    )
    (net (code "78") (name "unconnected-(BATERY_3-Pad2)") (class "Default")
      (node (ref "BATERY_3") (pin "2") (pinfunction "2_2") (pintype "bidirectional"))
    )
    (net (code "79") (name "unconnected-(BATERY_3-Pad4)") (class "Default")
      (node (ref "BATERY_3") (pin "4") (pinfunction "4_4") (pintype "bidirectional"))
    )
    (net (code "80") (name "unconnected-(JP9-Pad10)") (class "Default")
      (node (ref "JP9") (pin "10") (pinfunction "10_10") (pintype "passive"))
    )
    (net (code "81") (name "unconnected-(KICKER-Pad5)") (class "Default")
      (node (ref "KICKER") (pin "5") (pinfunction "5_5") (pintype "passive"))
    )
    (net (code "82") (name "unconnected-(LINE_SISTEM-Pad5)") (class "Default")
      (node (ref "LINE_SISTEM") (pin "5") (pinfunction "5_5") (pintype "passive"))
    )
    (net (code "83") (name "unconnected-(MAIN_POWER-3-ON-Pad3)") (class "Default")
      (node (ref "MAIN_POWER") (pin "3") (pinfunction "3-ON_3") (pintype "passive"))
    )
    (net (code "84") (name "unconnected-(MOTOR-3-ON-Pad3)") (class "Default")
      (node (ref "MOTOR") (pin "3") (pinfunction "3-ON_3") (pintype "passive"))
    )
    (net (code "85") (name "unconnected-(SMALL_LINE-Pad5)") (class "Default")
      (node (ref "SMALL_LINE") (pin "5") (pinfunction "5_5") (pintype "passive"))
    )
    (net (code "86") (name "unconnected-(U$4-PadCS)") (class "Default")
      (node (ref "U$4") (pin "CS") (pinfunction "CS_CS") (pintype "bidirectional"))
    )
    (net (code "87") (name "unconnected-(U$4-PadENA{slash}DIAGA)") (class "Default")
      (node (ref "U$4") (pin "ENA/DIAGA") (pinfunction "ENA/DIAGA_ENA/DIAGA") (pintype "bidirectional"))
    )
    (net (code "88") (name "unconnected-(U$4-PadENB{slash}DIAGB)") (class "Default")
      (node (ref "U$4") (pin "ENB/DIAGB") (pinfunction "ENB/DIAGB_ENB/DIAGB") (pintype "bidirectional"))
    )
    (net (code "89") (name "unconnected-(U$4-PadVOUT)") (class "Default")
      (node (ref "U$4") (pin "VOUT") (pinfunction "VOUT_VOUT") (pintype "bidirectional"))
    )
    (net (code "90") (name "unconnected-(U1-ADC6-Pad19)") (class "Default")
      (node (ref "U1") (pin "19") (pinfunction "ADC6_19") (pintype "bidirectional"))
    )
    (net (code "91") (name "unconnected-(U1-ADC7-Pad22)") (class "Default")
      (node (ref "U1") (pin "22") (pinfunction "ADC7_22") (pintype "bidirectional"))
    )
    (net (code "92") (name "unconnected-(U1-AREF-Pad20)") (class "Default")
      (node (ref "U1") (pin "20") (pinfunction "AREF_20") (pintype "bidirectional"))
    )
    (net (code "93") (name "unconnected-(U1-PB0(ICP)-Pad12)") (class "Default")
      (node (ref "U1") (pin "12") (pinfunction "PB0(ICP)_12") (pintype "bidirectional"))
    )
    (net (code "94") (name "unconnected-(U1-PB1(OC1A)-Pad13)") (class "Default")
      (node (ref "U1") (pin "13") (pinfunction "PB1(OC1A)_13") (pintype "bidirectional"))
    )
    (net (code "95") (name "unconnected-(U1-PC0(ADC0)-Pad23)") (class "Default")
      (node (ref "U1") (pin "23") (pinfunction "PC0(ADC0)_23") (pintype "bidirectional"))
    )
    (net (code "96") (name "unconnected-(U1-PC1(ADC1)-Pad24)") (class "Default")
      (node (ref "U1") (pin "24") (pinfunction "PC1(ADC1)_24") (pintype "bidirectional"))
    )
    (net (code "97") (name "unconnected-(U1-PC2(ADC2)-Pad25)") (class "Default")
      (node (ref "U1") (pin "25") (pinfunction "PC2(ADC2)_25") (pintype "bidirectional"))
    )
    (net (code "98") (name "unconnected-(U1-PC3(ADC3)-Pad26)") (class "Default")
      (node (ref "U1") (pin "26") (pinfunction "PC3(ADC3)_26") (pintype "bidirectional"))
    )
    (net (code "99") (name "unconnected-(U1-PC4(ADC4{slash}SDA)-Pad27)") (class "Default")
      (node (ref "U1") (pin "27") (pinfunction "PC4(ADC4/SDA)_27") (pintype "bidirectional"))
    )
    (net (code "100") (name "unconnected-(U1-PC5(ADC5{slash}SCL)-Pad28)") (class "Default")
      (node (ref "U1") (pin "28") (pinfunction "PC5(ADC5/SCL)_28") (pintype "bidirectional"))
    )
    (net (code "101") (name "unconnected-(U1-PD2(INT0)-Pad32)") (class "Default")
      (node (ref "U1") (pin "32") (pinfunction "PD2(INT0)_32") (pintype "bidirectional"))
    )
    (net (code "102") (name "unconnected-(U1-PD3(INT1)-Pad1)") (class "Default")
      (node (ref "U1") (pin "1") (pinfunction "PD3(INT1)_1") (pintype "bidirectional"))
    )
    (net (code "103") (name "unconnected-(U1-PD4(XCK{slash}T0)-Pad2)") (class "Default")
      (node (ref "U1") (pin "2") (pinfunction "PD4(XCK/T0)_2") (pintype "bidirectional"))
    )
    (net (code "104") (name "unconnected-(U2-ADC6-Pad19)") (class "Default")
      (node (ref "U2") (pin "19") (pinfunction "ADC6_19") (pintype "bidirectional"))
    )
    (net (code "105") (name "unconnected-(U2-ADC7-Pad22)") (class "Default")
      (node (ref "U2") (pin "22") (pinfunction "ADC7_22") (pintype "bidirectional"))
    )
    (net (code "106") (name "unconnected-(U2-AREF-Pad20)") (class "Default")
      (node (ref "U2") (pin "20") (pinfunction "AREF_20") (pintype "bidirectional"))
    )
    (net (code "107") (name "unconnected-(U2-PC1(ADC1)-Pad24)") (class "Default")
      (node (ref "U2") (pin "24") (pinfunction "PC1(ADC1)_24") (pintype "bidirectional"))
    )
    (net (code "108") (name "unconnected-(U2-PC2(ADC2)-Pad25)") (class "Default")
      (node (ref "U2") (pin "25") (pinfunction "PC2(ADC2)_25") (pintype "bidirectional"))
    )
    (net (code "109") (name "unconnected-(U2-PC3(ADC3)-Pad26)") (class "Default")
      (node (ref "U2") (pin "26") (pinfunction "PC3(ADC3)_26") (pintype "bidirectional"))
    )
    (net (code "110") (name "unconnected-(ULTRA_SISTEM-Pad5)") (class "Default")
      (node (ref "ULTRA_SISTEM") (pin "5") (pinfunction "5_5") (pintype "passive"))
    )
  )
)
